# working.net
KiCad netlist of a schematic drawn in EAGLE
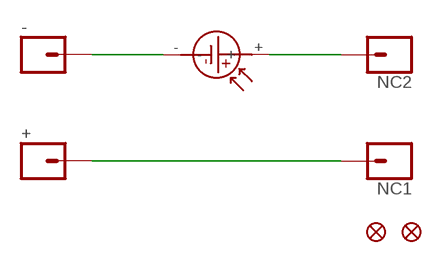
[diagram p0: schematic, sheet 1]

(export (version "E")
  (design (tool "Eeschema 10.0.6"))
  (components
    (comp (ref "+")
      (value "CONN_01")
      (footprint "eagle-import:1X01")
      (libsource (lib "eagle-import") (part "CONN_01"))
    )
    (comp (ref "-")
      (value "CONN_01")
      (footprint "eagle-import:1X01")
      (libsource (lib "eagle-import") (part "CONN_01"))
    )
    (comp (ref "FD1")
      (value "FIDUCIALUFIDUCIAL")
      (footprint "eagle-import:FIDUCIAL-MICRO")
      (libsource (lib "eagle-import") (part "FIDUCIALUFIDUCIAL"))
    )
    (comp (ref "FD2")
      (value "FIDUCIALUFIDUCIAL")
      (footprint "eagle-import:FIDUCIAL-MICRO")
      (libsource (lib "eagle-import") (part "FIDUCIALUFIDUCIAL"))
    )
    (comp (ref "NC1")
      (value "CONN_01")
      (footprint "eagle-import:1X01")
      (libsource (lib "eagle-import") (part "CONN_01"))
    )
    (comp (ref "NC2")
      (value "CONN_01")
      (footprint "eagle-import:1X01")
      (libsource (lib "eagle-import") (part "CONN_01"))
    )
    (comp (ref "U$1")
      (value "9X20_AMORPHOUS_PV")
      (footprint "eagle-import:20X9MM")
      (libsource (lib "eagle-import") (part "9X20_AMORPHOUS_PV"))
    )
  )
  (nets
    (net (code "1") (name "Net-(+-Pad1)") (class "Default")
      (node (ref "+") (pin "1") (pinfunction "1_1") (pintype "passive"))
      (node (ref "NC1") (pin "1") (pinfunction "1_1") (pintype "passive"))
    )
    (net (code "2") (name "Net-(--Pad1)") (class "Default")
      (node (ref "-") (pin "1") (pinfunction "1_1") (pintype "passive"))
      (node (ref "U$1") (pin "-") (pinfunction "-_-") (pintype "power_in"))
    )
    (net (code "3") (name "Net-(NC2-Pad1)") (class "Default")
      (node (ref "NC2") (pin "1") (pinfunction "1_1") (pintype "passive"))
      (node (ref "U$1") (pin "+") (pinfunction "+_+") (pintype "power_in"))
    )
  )
)
